# standalone_mod.net
KiCad netlist of a schematic drawn in EAGLE
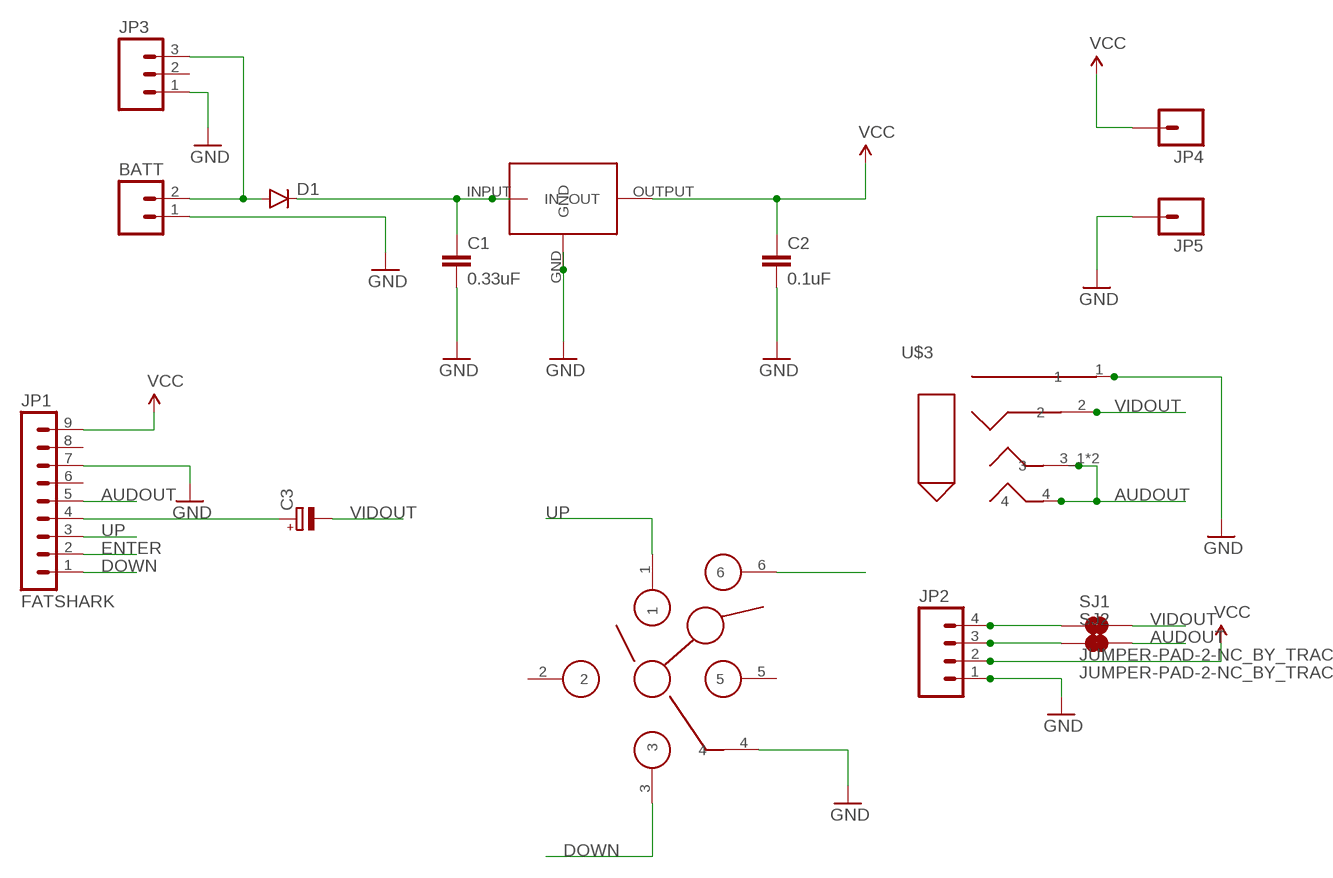
[diagram p0: schematic, sheet 1]

(export (version "E")
  (design (tool "Eeschema 10.0.6"))
  (components
    (comp (ref "BATT")
      (value "M02LOCK_LONGPADS")
      (footprint "eagle-import:1X02_LOCK_LONGPADS")
      (libsource (lib "eagle-import") (part "M02LOCK_LONGPADS"))
    )
    (comp (ref "C1")
      (value "0.33uF")
      (footprint "eagle-import:0805")
      (libsource (lib "eagle-import") (part "CAP0805"))
    )
    (comp (ref "C2")
      (value "0.1uF")
      (footprint "eagle-import:0805")
      (libsource (lib "eagle-import") (part "CAP0805"))
    )
    (comp (ref "C3")
      (value "CPOL-EUE3.5-8")
      (footprint "eagle-import:E3,5-8")
      (libsource (lib "eagle-import") (part "CPOL-EUE3.5-8"))
    )
    (comp (ref "D1")
      (value "DIODESMA")
      (footprint "eagle-import:SMA-DIODE")
      (libsource (lib "eagle-import") (part "DIODESMA"))
    )
    (comp (ref "JP1")
      (value "FATSHARK")
      (footprint "eagle-import:MA09-1")
      (libsource (lib "eagle-import") (part "MA09-1"))
    )
    (comp (ref "JP2")
      (value "M04PTH")
      (footprint "eagle-import:1X04")
      (libsource (lib "eagle-import") (part "M04PTH"))
    )
    (comp (ref "JP3")
      (value "M03LONGPADS")
      (footprint "eagle-import:1X03_LONGPADS")
      (libsource (lib "eagle-import") (part "M03LONGPADS"))
    )
    (comp (ref "JP4")
      (value "M01SMD")
      (footprint "eagle-import:LUXEON-PAD")
      (libsource (lib "eagle-import") (part "M01SMD"))
    )
    (comp (ref "JP5")
      (value "M01SMD")
      (footprint "eagle-import:LUXEON-PAD")
      (libsource (lib "eagle-import") (part "M01SMD"))
    )
    (comp (ref "SJ1")
      (value "JUMPER-PAD-2-NC_BY_TRACE")
      (footprint "eagle-import:PAD-JUMPER-2-NC_BY_TRACE_YES_SILK")
      (libsource (lib "eagle-import") (part "JUMPER-PAD-2-NC_BY_TRACE"))
    )
    (comp (ref "SJ2")
      (value "JUMPER-PAD-2-NC_BY_TRACE")
      (footprint "eagle-import:PAD-JUMPER-2-NC_BY_TRACE_YES_SILK")
      (libsource (lib "eagle-import") (part "JUMPER-PAD-2-NC_BY_TRACE"))
    )
    (comp (ref "U$1")
      (value "7805")
      (footprint "eagle-import:DDPAK")
      (libsource (lib "eagle-import") (part "7805"))
    )
    (comp (ref "U$2")
      (value "SKQUCAA010")
      (footprint "eagle-import:SKQUCAA010")
      (libsource (lib "eagle-import") (part "SKQUCAA010"))
    )
    (comp (ref "U$3")
      (value "MC001293JACK")
      (footprint "eagle-import:MC001293")
      (libsource (lib "eagle-import") (part "MC001293JACK"))
    )
  )
  (nets
    (net (code "1") (name "/AUDOUT") (class "Default")
      (node (ref "JP1") (pin "5") (pinfunction "5_5") (pintype "passive"))
      (node (ref "SJ2") (pin "2") (pinfunction "2_2") (pintype "passive"))
      (node (ref "U$3") (pin "3_1") (pinfunction "3_3_1") (pintype "bidirectional"))
      (node (ref "U$3") (pin "3_2") (pinfunction "3_3_2") (pintype "bidirectional"))
      (node (ref "U$3") (pin "4") (pinfunction "4_4") (pintype "bidirectional"))
    )
    (net (code "2") (name "/DOWN") (class "Default")
      (node (ref "JP1") (pin "1") (pinfunction "1_1") (pintype "passive"))
      (node (ref "U$2") (pin "3") (pinfunction "3_3") (pintype "bidirectional"))
    )
    (net (code "3") (name "/ENTER") (class "Default")
      (node (ref "JP1") (pin "2") (pinfunction "2_2") (pintype "passive"))
      (node (ref "U$2") (pin "6") (pinfunction "6_6") (pintype "bidirectional"))
    )
    (net (code "4") (name "/UP") (class "Default")
      (node (ref "JP1") (pin "3") (pinfunction "3_3") (pintype "passive"))
      (node (ref "U$2") (pin "1") (pinfunction "1_1") (pintype "bidirectional"))
    )
    (net (code "5") (name "/VIDOUT") (class "Default")
      (node (ref "C3") (pin "-") (pinfunction "-_-") (pintype "passive"))
      (node (ref "SJ1") (pin "2") (pinfunction "2_2") (pintype "passive"))
      (node (ref "U$3") (pin "2") (pinfunction "2_2") (pintype "bidirectional"))
    )
    (net (code "6") (name "GND") (class "Default")
      (node (ref "BATT") (pin "1") (pinfunction "1_1") (pintype "passive"))
      (node (ref "C1") (pin "2") (pinfunction "2_2") (pintype "passive"))
      (node (ref "C2") (pin "2") (pinfunction "2_2") (pintype "passive"))
      (node (ref "JP1") (pin "7") (pinfunction "7_7") (pintype "passive"))
      (node (ref "JP2") (pin "1") (pinfunction "1_1") (pintype "passive"))
      (node (ref "JP3") (pin "1") (pinfunction "1_1") (pintype "passive"))
      (node (ref "JP5") (pin "P$1") (pinfunction "1_P$1") (pintype "passive"))
      (node (ref "U$1") (pin "GND") (pinfunction "GND_GND") (pintype "bidirectional"))
      (node (ref "U$2") (pin "4") (pinfunction "4_4") (pintype "bidirectional"))
      (node (ref "U$3") (pin "1") (pinfunction "1_1") (pintype "bidirectional"))
    )
    (net (code "7") (name "Net-(BATT-Pad2)") (class "Default")
      (node (ref "BATT") (pin "2") (pinfunction "2_2") (pintype "passive"))
      (node (ref "D1") (pin "A") (pinfunction "A_A") (pintype "passive"))
      (node (ref "JP3") (pin "3") (pinfunction "3_3") (pintype "passive"))
    )
    (net (code "8") (name "Net-(C3-Pad+)") (class "Default")
      (node (ref "C3") (pin "+") (pinfunction "+_+") (pintype "passive"))
      (node (ref "JP1") (pin "4") (pinfunction "4_4") (pintype "passive"))
    )
    (net (code "9") (name "Net-(JP2-Pad3)") (class "Default")
      (node (ref "JP2") (pin "3") (pinfunction "3_3") (pintype "passive"))
      (node (ref "SJ2") (pin "1") (pinfunction "1_1") (pintype "passive"))
    )
    (net (code "10") (name "Net-(JP2-Pad4)") (class "Default")
      (node (ref "JP2") (pin "4") (pinfunction "4_4") (pintype "passive"))
      (node (ref "SJ1") (pin "1") (pinfunction "1_1") (pintype "passive"))
    )
    (net (code "11") (name "Net-(U$1-IN)") (class "Default")
      (node (ref "C1") (pin "1") (pinfunction "1_1") (pintype "passive"))
      (node (ref "D1") (pin "C") (pinfunction "C_C") (pintype "passive"))
      (node (ref "U$1") (pin "INPUT") (pinfunction "IN_INPUT") (pintype "bidirectional"))
    )
    (net (code "12") (name "VCC") (class "Default")
      (node (ref "C2") (pin "1") (pinfunction "1_1") (pintype "passive"))
      (node (ref "JP1") (pin "9") (pinfunction "9_9") (pintype "passive"))
      (node (ref "JP2") (pin "2") (pinfunction "2_2") (pintype "passive"))
      (node (ref "JP4") (pin "P$1") (pinfunction "1_P$1") (pintype "passive"))
      (node (ref "U$1") (pin "OUTPUT") (pinfunction "OUT_OUTPUT") (pintype "bidirectional"))
    )
    (net (code "13") (name "unconnected-(JP1-Pad6)") (class "Default")
      (node (ref "JP1") (pin "6") (pinfunction "6_6") (pintype "passive"))
    )
    (net (code "14") (name "unconnected-(JP1-Pad8)") (class "Default")
      (node (ref "JP1") (pin "8") (pinfunction "8_8") (pintype "passive"))
    )
    (net (code "15") (name "unconnected-(JP3-Pad2)") (class "Default")
      (node (ref "JP3") (pin "2") (pinfunction "2_2") (pintype "passive"))
    )
    (net (code "16") (name "unconnected-(U$2-Pad2)") (class "Default")
      (node (ref "U$2") (pin "2") (pinfunction "2_2") (pintype "bidirectional"))
    )
    (net (code "17") (name "unconnected-(U$2-Pad5)") (class "Default")
      (node (ref "U$2") (pin "5") (pinfunction "5_5") (pintype "bidirectional"))
    )
  )
)
